# Precharge.net
KiCad netlist of a schematic drawn in Altium Designer
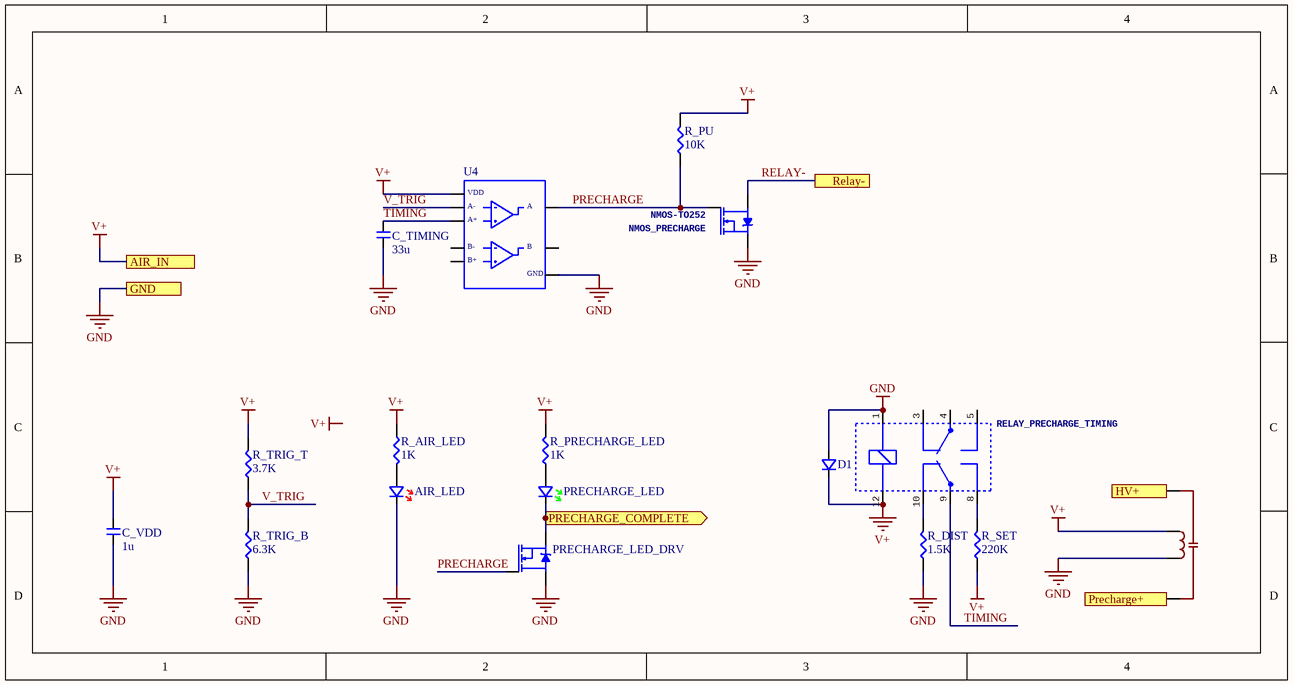
[diagram p0: Precharge.SchDoc]

(export (version "E")
  (design (tool "Eeschema 10.0.6"))
  (components
    (comp (ref "AIR_LED")
      (value "~")
      (footprint "LEDRED-0603")
      (libsource (lib "altium-import") (part "root_3_LEDRED-0603_"))
    )
    (comp (ref "C_TIMING")
      (value "33u")
      (footprint "CAP-0603")
      (libsource (lib "altium-import") (part "root_1_CAP-0603_"))
    )
    (comp (ref "C_VDD")
      (value "1u")
      (footprint "CAP-0603")
      (libsource (lib "altium-import") (part "root_1_CAP-0603_"))
    )
    (comp (ref "D1")
      (value "~")
      (footprint "DO41-10")
      (libsource (lib "altium-import") (part "root_3_DIODE-DO41-10_"))
    )
    (comp (ref "NMOS_PRECHARGE")
      (value "NMOS-TO252")
      (footprint "TO252")
      (libsource (lib "ife19_Elec_Library") (part "NMOS-TO252"))
    )
    (comp (ref "PRECHARGE_LED")
      (value "~")
      (footprint "LEDGREEN-0603")
      (libsource (lib "altium-import") (part "root_3_LEDGREEN-0603_"))
    )
    (comp (ref "PRECHARGE_LED_DRV")
      (value "~")
      (footprint "SOT23")
      (libsource (lib "altium-import") (part "root_0_mirrored_NMOS-SOT23_"))
    )
    (comp (ref "RELAY_PRECHARGE")
      (value "COTO9104")
      (footprint "9104-SIP4")
      (fields (field (name "LIBRARYNAME") "Discharge_Components_Altium_Export"))
      (libsource (lib "altium-import") (part "root_3_COTO9104_"))
    )
    (comp (ref "RELAY_PRECHARGE_TIMING")
      (value "~")
      (footprint "RELAY-DPDT_EC2")
      (libsource (lib "altium-import") (part "root_0_RELAY_EC2_"))
    )
    (comp (ref "R_AIR_LED")
      (value "1K")
      (footprint "RES-0603")
      (libsource (lib "altium-import") (part "root_3_RES-0603_"))
    )
    (comp (ref "R_DIST")
      (value "1.5K")
      (footprint "RES-0603")
      (libsource (lib "ife19_Elec_Library") (part "RES-0603"))
    )
    (comp (ref "R_PRECHARGE_LED")
      (value "1K")
      (footprint "RES-0603")
      (libsource (lib "altium-import") (part "root_1_RES-0603_"))
    )
    (comp (ref "R_PU")
      (value "10K")
      (footprint "RES-0603")
      (libsource (lib "altium-import") (part "root_1_RES-0603_"))
    )
    (comp (ref "R_SET")
      (value "220K")
      (footprint "RES-0603")
      (libsource (lib "ife19_Elec_Library") (part "RES-0603"))
    )
    (comp (ref "R_TRIG_B")
      (value "6.3K")
      (footprint "RES-0603")
      (libsource (lib "altium-import") (part "root_1_RES-0603_"))
    )
    (comp (ref "R_TRIG_T")
      (value "3.7K")
      (footprint "RES-0603")
      (libsource (lib "altium-import") (part "root_1_RES-0603_"))
    )
    (comp (ref "U4")
      (value "~")
      (footprint "SOIC8")
      (libsource (lib "altium-import") (part "root_0_IC-SOIC8_LM393_"))
    )
  )
  (nets
    (net (code "1") (name "/HV+") (class "Default")
      (node (ref "RELAY_PRECHARGE") (pin "1") (pinfunction "1_1") (pintype "passive"))
    )
    (net (code "2") (name "/PRECHARGE") (class "Default")
      (node (ref "NMOS_PRECHARGE") (pin "1") (pinfunction "G_1") (pintype "passive"))
      (node (ref "PRECHARGE_LED_DRV") (pin "1") (pinfunction "G_1") (pintype "passive"))
      (node (ref "R_PU") (pin "1") (pinfunction "1_1") (pintype "passive"))
      (node (ref "U4") (pin "1") (pinfunction "1_1") (pintype "passive"))
    )
    (net (code "3") (name "/PRECHARGE_COMPLETE") (class "Default")
      (node (ref "PRECHARGE_LED") (pin "K") (pinfunction "K_K") (pintype "passive"))
      (node (ref "PRECHARGE_LED_DRV") (pin "3") (pinfunction "D_3") (pintype "passive"))
    )
    (net (code "4") (name "/Precharge+") (class "Default")
      (node (ref "RELAY_PRECHARGE") (pin "7") (pinfunction "7_7") (pintype "passive"))
    )
    (net (code "5") (name "/RELAY-") (class "Default")
      (node (ref "NMOS_PRECHARGE") (pin "2") (pinfunction "S_2") (pintype "passive"))
    )
    (net (code "6") (name "/TIMING") (class "Default")
      (node (ref "C_TIMING") (pin "2") (pinfunction "2_2") (pintype "passive"))
      (node (ref "RELAY_PRECHARGE_TIMING") (pin "9") (pintype "passive"))
      (node (ref "U4") (pin "3") (pinfunction "3_3") (pintype "passive"))
    )
    (net (code "7") (name "/V_TRIG") (class "Default")
      (node (ref "R_TRIG_B") (pin "2") (pinfunction "2_2") (pintype "passive"))
      (node (ref "R_TRIG_T") (pin "1") (pinfunction "1_1") (pintype "passive"))
      (node (ref "U4") (pin "2") (pinfunction "2_2") (pintype "passive"))
    )
    (net (code "8") (name "GND") (class "Default")
      (node (ref "AIR_LED") (pin "K") (pinfunction "K_K") (pintype "passive"))
      (node (ref "C_TIMING") (pin "1") (pinfunction "1_1") (pintype "passive"))
      (node (ref "C_VDD") (pin "1") (pinfunction "1_1") (pintype "passive"))
      (node (ref "D1") (pin "A") (pinfunction "A_A") (pintype "passive"))
      (node (ref "NMOS_PRECHARGE") (pin "3") (pinfunction "D_3") (pintype "passive"))
      (node (ref "PRECHARGE_LED_DRV") (pin "2") (pinfunction "S_2") (pintype "passive"))
      (node (ref "RELAY_PRECHARGE") (pin "5") (pinfunction "5_5") (pintype "passive"))
      (node (ref "RELAY_PRECHARGE_TIMING") (pin "1") (pintype "passive"))
      (node (ref "R_DIST") (pin "2") (pinfunction "2_2") (pintype "passive"))
      (node (ref "R_TRIG_B") (pin "1") (pinfunction "1_1") (pintype "passive"))
      (node (ref "U4") (pin "4") (pinfunction "4_4") (pintype "passive"))
    )
    (net (code "9") (name "Net-(AIR_LED-PadA)") (class "Default")
      (node (ref "AIR_LED") (pin "A") (pinfunction "A_A") (pintype "passive"))
      (node (ref "R_AIR_LED") (pin "2") (pinfunction "2_2") (pintype "passive"))
    )
    (net (code "10") (name "Net-(PRECHARGE_LED-PadA)") (class "Default")
      (node (ref "PRECHARGE_LED") (pin "A") (pinfunction "A_A") (pintype "passive"))
      (node (ref "R_PRECHARGE_LED") (pin "1") (pinfunction "1_1") (pintype "passive"))
    )
    (net (code "11") (name "Net-(RELAY_PRECHARGE_TIMING-Pad8)") (class "Default")
      (node (ref "RELAY_PRECHARGE_TIMING") (pin "8") (pintype "passive"))
      (node (ref "R_SET") (pin "1") (pinfunction "1_1") (pintype "passive"))
    )
    (net (code "12") (name "Net-(RELAY_PRECHARGE_TIMING-Pad10)") (class "Default")
      (node (ref "RELAY_PRECHARGE_TIMING") (pin "10") (pintype "passive"))
      (node (ref "R_DIST") (pin "1") (pinfunction "1_1") (pintype "passive"))
    )
    (net (code "13") (name "V+") (class "Default")
      (node (ref "C_VDD") (pin "2") (pinfunction "2_2") (pintype "passive"))
      (node (ref "D1") (pin "K") (pinfunction "K_K") (pintype "passive"))
      (node (ref "RELAY_PRECHARGE") (pin "3") (pinfunction "3_3") (pintype "passive"))
      (node (ref "RELAY_PRECHARGE_TIMING") (pin "12") (pintype "passive"))
      (node (ref "R_AIR_LED") (pin "1") (pinfunction "1_1") (pintype "passive"))
      (node (ref "R_PRECHARGE_LED") (pin "2") (pinfunction "2_2") (pintype "passive"))
      (node (ref "R_PU") (pin "2") (pinfunction "2_2") (pintype "passive"))
      (node (ref "R_SET") (pin "2") (pinfunction "2_2") (pintype "passive"))
      (node (ref "R_TRIG_T") (pin "2") (pinfunction "2_2") (pintype "passive"))
      (node (ref "U4") (pin "8") (pinfunction "8_8") (pintype "passive"))
    )
    (net (code "14") (name "unconnected-(RELAY_PRECHARGE_TIMING-Pad3)") (class "Default")
      (node (ref "RELAY_PRECHARGE_TIMING") (pin "3") (pintype "passive"))
    )
    (net (code "15") (name "unconnected-(RELAY_PRECHARGE_TIMING-Pad4)") (class "Default")
      (node (ref "RELAY_PRECHARGE_TIMING") (pin "4") (pintype "passive"))
    )
    (net (code "16") (name "unconnected-(RELAY_PRECHARGE_TIMING-Pad5)") (class "Default")
      (node (ref "RELAY_PRECHARGE_TIMING") (pin "5") (pintype "passive"))
    )
    (net (code "17") (name "unconnected-(U4-Pad5)") (class "Default")
      (node (ref "U4") (pin "5") (pinfunction "5_5") (pintype "passive"))
    )
    (net (code "18") (name "unconnected-(U4-Pad6)") (class "Default")
      (node (ref "U4") (pin "6") (pinfunction "6_6") (pintype "passive"))
    )
    (net (code "19") (name "unconnected-(U4-Pad7)") (class "Default")
      (node (ref "U4") (pin "7") (pinfunction "7_7") (pintype "passive"))
    )
  )
)
